# MB_RELAY.net
KiCad netlist of a schematic drawn in Altium Designer
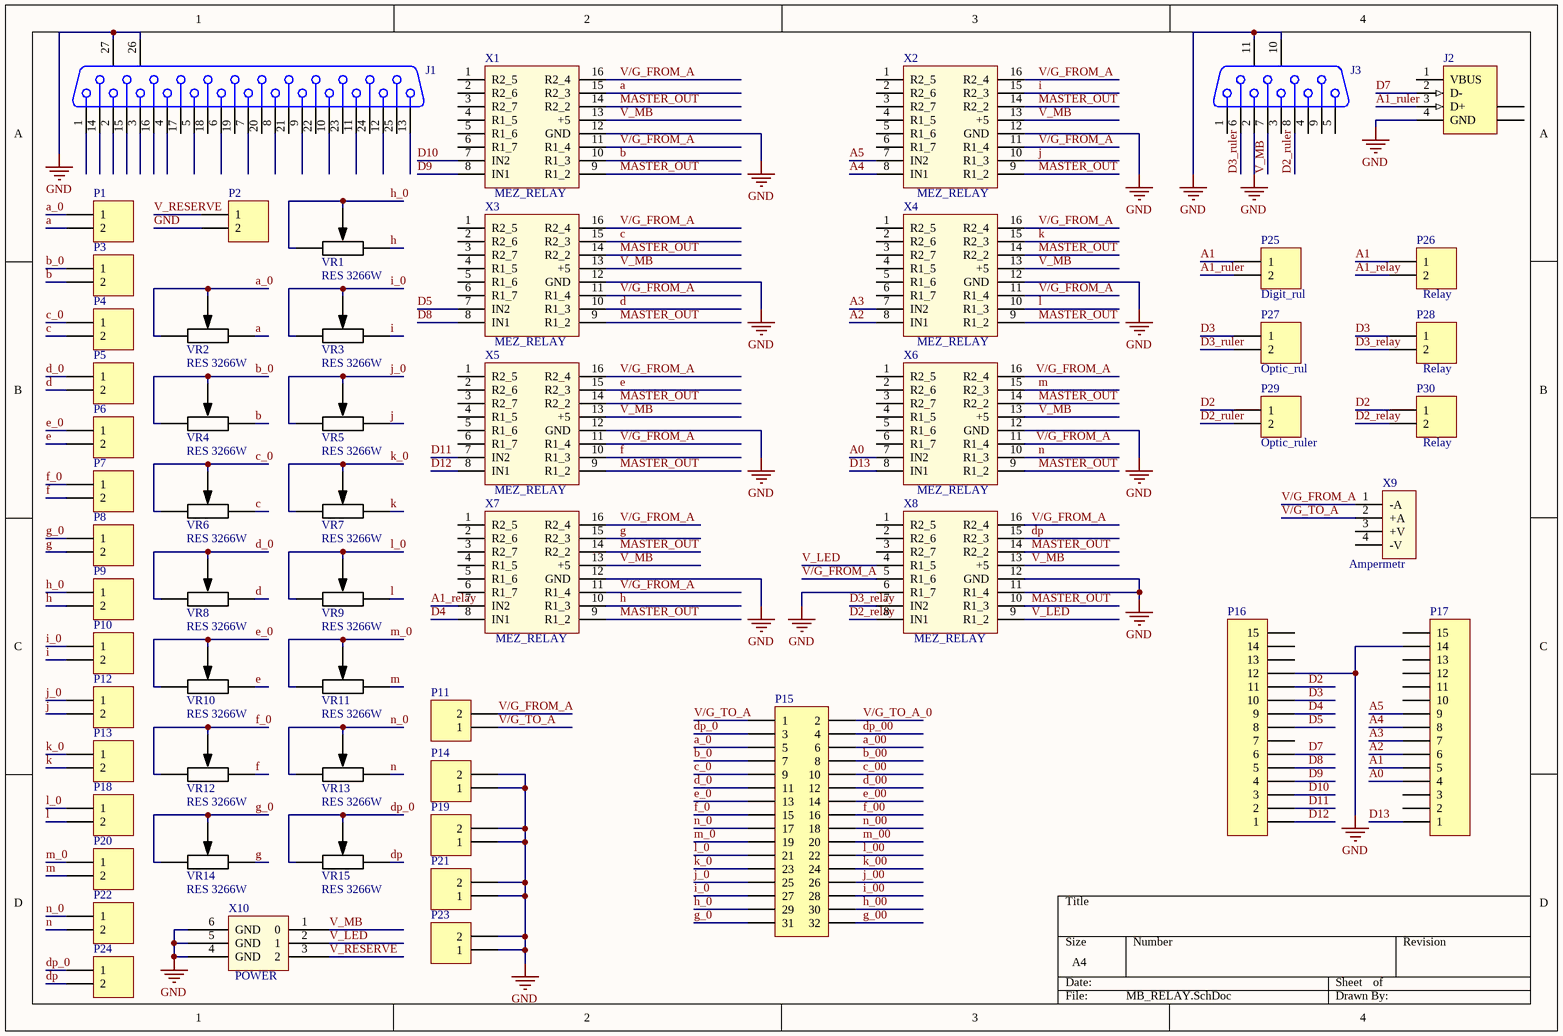
[diagram p0: MB_RELAY.SchDoc]

(export (version "E")
  (design (tool "Eeschema 10.0.6"))
  (components
    (comp (ref "J1")
      (value "D Connector 25")
      (footprint "DSUB1.385-2H25A")
      (description "Receptacle Assembly, 25 Position, Right Angle")
      (fields (field (name "PUBLISHER") "Altium Limited"))
      (libsource (lib "Miscellaneous Connectors") (part "D Connector 25"))
    )
    (comp (ref "J2")
      (value "1-353576-1")
      (footprint "353576")
      (description "USB 1.1, Right Angle, SMT, A Type, Receptacle, 4 Position, White")
      (fields (field (name "PUBLISHER") "Altium Limited"))
      (libsource (lib "AMP Serial Bus USB") (part "1-353576-1"))
    )
    (comp (ref "J3")
      (value "D Connector 9")
      (footprint "DSUB1.385-2H9")
      (description "Receptacle Assembly, 9 Position, Right Angle")
      (fields (field (name "PUBLISHER") "Altium Limited"))
      (libsource (lib "Miscellaneous Connectors") (part "D Connector 9"))
    )
    (comp (ref "P1")
      (value "Header 2")
      (footprint "HDR1X2")
      (description "Header, 2-Pin")
      (fields (field (name "PUBLISHER") "Altium Limited"))
      (libsource (lib "Miscellaneous Connectors") (part "Header 2"))
    )
    (comp (ref "P2")
      (value "Header 2")
      (footprint "HDR1X2")
      (description "Header, 2-Pin")
      (fields (field (name "PUBLISHER") "Altium Limited"))
      (libsource (lib "Miscellaneous Connectors") (part "Header 2"))
    )
    (comp (ref "P3")
      (value "Header 2")
      (footprint "HDR1X2")
      (description "Header, 2-Pin")
      (fields (field (name "PUBLISHER") "Altium Limited"))
      (libsource (lib "Miscellaneous Connectors") (part "Header 2"))
    )
    (comp (ref "P4")
      (value "Header 2")
      (footprint "HDR1X2")
      (description "Header, 2-Pin")
      (fields (field (name "PUBLISHER") "Altium Limited"))
      (libsource (lib "Miscellaneous Connectors") (part "Header 2"))
    )
    (comp (ref "P5")
      (value "Header 2")
      (footprint "HDR1X2")
      (description "Header, 2-Pin")
      (fields (field (name "PUBLISHER") "Altium Limited"))
      (libsource (lib "Miscellaneous Connectors") (part "Header 2"))
    )
    (comp (ref "P6")
      (value "GND")
      (footprint "HDR1X2")
      (description "Header, 2-Pin")
      (fields (field (name "PUBLISHER") "Altium Limited"))
      (libsource (lib "Miscellaneous Connectors") (part "Header 2"))
    )
    (comp (ref "P7")
      (value "GND")
      (footprint "HDR1X2")
      (description "Header, 2-Pin")
      (fields (field (name "PUBLISHER") "Altium Limited"))
      (libsource (lib "Miscellaneous Connectors") (part "Header 2"))
    )
    (comp (ref "P8")
      (value "GND")
      (footprint "HDR1X2")
      (description "Header, 2-Pin")
      (fields (field (name "PUBLISHER") "Altium Limited"))
      (libsource (lib "Miscellaneous Connectors") (part "Header 2"))
    )
    (comp (ref "P9")
      (value "GND")
      (footprint "HDR1X2")
      (description "Header, 2-Pin")
      (fields (field (name "PUBLISHER") "Altium Limited"))
      (libsource (lib "Miscellaneous Connectors") (part "Header 2"))
    )
    (comp (ref "P10")
      (value "Header 2")
      (footprint "HDR1X2")
      (description "Header, 2-Pin")
      (fields (field (name "PUBLISHER") "Altium Limited"))
      (libsource (lib "Miscellaneous Connectors") (part "Header 2"))
    )
    (comp (ref "P11")
      (value "Header 2")
      (footprint "HDR1X2")
      (description "Header, 2-Pin")
      (fields (field (name "PUBLISHER") "Altium Limited"))
      (libsource (lib "") (part "Header 2_1"))
    )
    (comp (ref "P12")
      (value "Header 2")
      (footprint "HDR1X2")
      (description "Header, 2-Pin")
      (fields (field (name "PUBLISHER") "Altium Limited"))
      (libsource (lib "Miscellaneous Connectors") (part "Header 2"))
    )
    (comp (ref "P13")
      (value "GND")
      (footprint "HDR1X2")
      (description "Header, 2-Pin")
      (fields (field (name "PUBLISHER") "Altium Limited"))
      (libsource (lib "Miscellaneous Connectors") (part "Header 2"))
    )
    (comp (ref "P14")
      (value "GND")
      (footprint "HDR1X2")
      (description "Header, 2-Pin")
      (fields (field (name "PUBLISHER") "Altium Limited"))
      (libsource (lib "") (part "Header 2_1"))
    )
    (comp (ref "P15")
      (value "Header 16X2")
      (footprint "HDR2X16")
      (description "Header, 16-Pin, Dual row")
      (fields (field (name "PUBLISHER") "Altium Limited"))
      (libsource (lib "Miscellaneous Connectors") (part "Header 16X2"))
    )
    (comp (ref "P16")
      (value "Header 15")
      (footprint "HDR1X15")
      (description "Header, 15-Pin")
      (fields (field (name "PUBLISHER") "Altium Limited"))
      (libsource (lib "") (part "Header 15_1"))
    )
    (comp (ref "P17")
      (value "Header 15")
      (footprint "HDR1X15")
      (description "Header, 15-Pin")
      (fields (field (name "PUBLISHER") "Altium Limited"))
      (libsource (lib "Miscellaneous Connectors") (part "Header 15"))
    )
    (comp (ref "P18")
      (value "GND")
      (footprint "HDR1X2")
      (description "Header, 2-Pin")
      (fields (field (name "PUBLISHER") "Altium Limited"))
      (libsource (lib "Miscellaneous Connectors") (part "Header 2"))
    )
    (comp (ref "P19")
      (value "GND")
      (footprint "HDR1X2")
      (description "Header, 2-Pin")
      (fields (field (name "PUBLISHER") "Altium Limited"))
      (libsource (lib "") (part "Header 2_1"))
    )
    (comp (ref "P20")
      (value "GND")
      (footprint "HDR1X2")
      (description "Header, 2-Pin")
      (fields (field (name "PUBLISHER") "Altium Limited"))
      (libsource (lib "Miscellaneous Connectors") (part "Header 2"))
    )
    (comp (ref "P21")
      (value "GND")
      (footprint "HDR1X2")
      (description "Header, 2-Pin")
      (fields (field (name "PUBLISHER") "Altium Limited"))
      (libsource (lib "") (part "Header 2_1"))
    )
    (comp (ref "P22")
      (value "GND")
      (footprint "HDR1X2")
      (description "Header, 2-Pin")
      (fields (field (name "PUBLISHER") "Altium Limited"))
      (libsource (lib "Miscellaneous Connectors") (part "Header 2"))
    )
    (comp (ref "P23")
      (value "GND")
      (footprint "HDR1X2")
      (description "Header, 2-Pin")
      (fields (field (name "PUBLISHER") "Altium Limited"))
      (libsource (lib "") (part "Header 2_1"))
    )
    (comp (ref "P24")
      (value "GND")
      (footprint "HDR1X2")
      (description "Header, 2-Pin")
      (fields (field (name "PUBLISHER") "Altium Limited"))
      (libsource (lib "Miscellaneous Connectors") (part "Header 2"))
    )
    (comp (ref "P25")
      (value "Digit_rul")
      (footprint "HDR1X2")
      (description "Header, 2-Pin")
      (fields (field (name "PUBLISHER") "Altium Limited"))
      (libsource (lib "Miscellaneous Connectors") (part "Header 2"))
    )
    (comp (ref "P26")
      (value "Relay")
      (footprint "HDR1X2")
      (description "Header, 2-Pin")
      (fields (field (name "PUBLISHER") "Altium Limited"))
      (libsource (lib "Miscellaneous Connectors") (part "Header 2"))
    )
    (comp (ref "P27")
      (value "Optic_rul")
      (footprint "HDR1X2")
      (description "Header, 2-Pin")
      (fields (field (name "PUBLISHER") "Altium Limited"))
      (libsource (lib "Miscellaneous Connectors") (part "Header 2"))
    )
    (comp (ref "P28")
      (value "Relay")
      (footprint "HDR1X2")
      (description "Header, 2-Pin")
      (fields (field (name "PUBLISHER") "Altium Limited"))
      (libsource (lib "Miscellaneous Connectors") (part "Header 2"))
    )
    (comp (ref "P29")
      (value "Optic_ruler")
      (footprint "HDR1X2")
      (description "Header, 2-Pin")
      (fields (field (name "PUBLISHER") "Altium Limited"))
      (libsource (lib "Miscellaneous Connectors") (part "Header 2"))
    )
    (comp (ref "P30")
      (value "Relay")
      (footprint "HDR1X2")
      (description "Header, 2-Pin")
      (fields (field (name "PUBLISHER") "Altium Limited"))
      (libsource (lib "Miscellaneous Connectors") (part "Header 2"))
    )
    (comp (ref "VR1")
      (value "RES 3266W")
      (footprint "aab_Passive:RES 3266W")
      (libsource (lib "aab_Schlib") (part "RES 3266W"))
    )
    (comp (ref "VR2")
      (value "RES 3266W")
      (footprint "aab_Passive:RES 3266W")
      (libsource (lib "aab_Schlib") (part "RES 3266W"))
    )
    (comp (ref "VR3")
      (value "RES 3266W")
      (footprint "aab_Passive:RES 3266W")
      (libsource (lib "aab_Schlib") (part "RES 3266W"))
    )
    (comp (ref "VR4")
      (value "RES 3266W")
      (footprint "aab_Passive:RES 3266W")
      (libsource (lib "aab_Schlib") (part "RES 3266W"))
    )
    (comp (ref "VR5")
      (value "RES 3266W")
      (footprint "aab_Passive:RES 3266W")
      (libsource (lib "aab_Schlib") (part "RES 3266W"))
    )
    (comp (ref "VR6")
      (value "RES 3266W")
      (footprint "aab_Passive:RES 3266W")
      (libsource (lib "aab_Schlib") (part "RES 3266W"))
    )
    (comp (ref "VR7")
      (value "RES 3266W")
      (footprint "aab_Passive:RES 3266W")
      (libsource (lib "aab_Schlib") (part "RES 3266W"))
    )
    (comp (ref "VR8")
      (value "RES 3266W")
      (footprint "aab_Passive:RES 3266W")
      (libsource (lib "aab_Schlib") (part "RES 3266W"))
    )
    (comp (ref "VR9")
      (value "RES 3266W")
      (footprint "aab_Passive:RES 3266W")
      (libsource (lib "aab_Schlib") (part "RES 3266W"))
    )
    (comp (ref "VR10")
      (value "RES 3266W")
      (footprint "aab_Passive:RES 3266W")
      (libsource (lib "aab_Schlib") (part "RES 3266W"))
    )
    (comp (ref "VR11")
      (value "RES 3266W")
      (footprint "aab_Passive:RES 3266W")
      (libsource (lib "aab_Schlib") (part "RES 3266W"))
    )
    (comp (ref "VR12")
      (value "RES 3266W")
      (footprint "aab_Passive:RES 3266W")
      (libsource (lib "aab_Schlib") (part "RES 3266W"))
    )
    (comp (ref "VR13")
      (value "RES 3266W")
      (footprint "aab_Passive:RES 3266W")
      (libsource (lib "aab_Schlib") (part "RES 3266W"))
    )
    (comp (ref "VR14")
      (value "RES 3266W")
      (footprint "aab_Passive:RES 3266W")
      (libsource (lib "aab_Schlib") (part "RES 3266W"))
    )
    (comp (ref "VR15")
      (value "RES 3266W")
      (footprint "aab_Passive:RES 3266W")
      (libsource (lib "aab_Schlib") (part "RES 3266W"))
    )
    (comp (ref "X1")
      (value "MEZ_RELAY")
      (footprint "MEZ_RELAY")
      (libsource (lib "msp_SchLib") (part "MEZ_RELAY"))
    )
    (comp (ref "X2")
      (value "MEZ_RELAY")
      (footprint "MEZ_RELAY")
      (libsource (lib "msp_SchLib") (part "MEZ_RELAY"))
    )
    (comp (ref "X3")
      (value "MEZ_RELAY")
      (footprint "MEZ_RELAY")
      (libsource (lib "msp_SchLib") (part "MEZ_RELAY"))
    )
    (comp (ref "X4")
      (value "MEZ_RELAY")
      (footprint "MEZ_RELAY")
      (libsource (lib "msp_SchLib") (part "MEZ_RELAY"))
    )
    (comp (ref "X5")
      (value "MEZ_RELAY")
      (footprint "MEZ_RELAY")
      (libsource (lib "msp_SchLib") (part "MEZ_RELAY"))
    )
    (comp (ref "X6")
      (value "MEZ_RELAY")
      (footprint "MEZ_RELAY")
      (libsource (lib "msp_SchLib") (part "MEZ_RELAY"))
    )
    (comp (ref "X7")
      (value "MEZ_RELAY")
      (footprint "MEZ_RELAY")
      (libsource (lib "msp_SchLib") (part "MEZ_RELAY"))
    )
    (comp (ref "X8")
      (value "MEZ_RELAY")
      (footprint "MEZ_RELAY")
      (libsource (lib "msp_SchLib") (part "MEZ_RELAY"))
    )
    (comp (ref "X9")
      (value "Ampermetr")
      (footprint "vpl_Passive:AMP_VOLTMETER")
      (libsource (lib "msp_SchLib") (part "AMP_VOLTMETR"))
    )
    (comp (ref "X10")
      (value "POWER")
      (footprint "vpl_Passive:POWER")
      (libsource (lib "msp_SchLib") (part "POWER"))
    )
  )
  (nets
    (net (code "1") (name "/A0") (class "Default")
      (node (ref "P17") (pin "4") (pinfunction "4_4") (pintype "passive"))
      (node (ref "X6") (pin "7") (pinfunction "IN2_7") (pintype "passive"))
    )
    (net (code "2") (name "/A1") (class "Default")
      (node (ref "P17") (pin "5") (pinfunction "5_5") (pintype "passive"))
      (node (ref "P25") (pin "1") (pinfunction "1_1") (pintype "passive"))
      (node (ref "P26") (pin "1") (pinfunction "1_1") (pintype "passive"))
    )
    (net (code "3") (name "/A1_relay") (class "Default")
      (node (ref "P26") (pin "2") (pinfunction "2_2") (pintype "passive"))
      (node (ref "X7") (pin "7") (pinfunction "IN2_7") (pintype "passive"))
    )
    (net (code "4") (name "/A1_ruler") (class "Default")
      (node (ref "J2") (pin "3") (pinfunction "D+_3") (pintype "input"))
      (node (ref "P25") (pin "2") (pinfunction "2_2") (pintype "passive"))
    )
    (net (code "5") (name "/A2") (class "Default")
      (node (ref "P17") (pin "6") (pinfunction "6_6") (pintype "passive"))
      (node (ref "X4") (pin "8") (pinfunction "IN1_8") (pintype "passive"))
    )
    (net (code "6") (name "/A3") (class "Default")
      (node (ref "P17") (pin "7") (pinfunction "7_7") (pintype "passive"))
      (node (ref "X4") (pin "7") (pinfunction "IN2_7") (pintype "passive"))
    )
    (net (code "7") (name "/A4") (class "Default")
      (node (ref "P17") (pin "8") (pinfunction "8_8") (pintype "passive"))
      (node (ref "X2") (pin "8") (pinfunction "IN1_8") (pintype "passive"))
    )
    (net (code "8") (name "/A5") (class "Default")
      (node (ref "P17") (pin "9") (pinfunction "9_9") (pintype "passive"))
      (node (ref "X2") (pin "7") (pinfunction "IN2_7") (pintype "passive"))
    )
    (net (code "9") (name "/D2") (class "Default")
      (node (ref "P16") (pin "11") (pinfunction "11_11") (pintype "passive"))
      (node (ref "P29") (pin "1") (pinfunction "1_1") (pintype "passive"))
      (node (ref "P30") (pin "1") (pinfunction "1_1") (pintype "passive"))
    )
    (net (code "10") (name "/D2_relay") (class "Default")
      (node (ref "P30") (pin "2") (pinfunction "2_2") (pintype "passive"))
      (node (ref "X8") (pin "8") (pinfunction "IN1_8") (pintype "passive"))
    )
    (net (code "11") (name "/D2_ruler") (class "Default")
      (node (ref "J3") (pin "8") (pinfunction "8_8") (pintype "passive"))
      (node (ref "P29") (pin "2") (pinfunction "2_2") (pintype "passive"))
    )
    (net (code "12") (name "/D3") (class "Default")
      (node (ref "P16") (pin "10") (pinfunction "10_10") (pintype "passive"))
      (node (ref "P27") (pin "1") (pinfunction "1_1") (pintype "passive"))
      (node (ref "P28") (pin "1") (pinfunction "1_1") (pintype "passive"))
    )
    (net (code "13") (name "/D3_relay") (class "Default")
      (node (ref "P28") (pin "2") (pinfunction "2_2") (pintype "passive"))
      (node (ref "X8") (pin "7") (pinfunction "IN2_7") (pintype "passive"))
    )
    (net (code "14") (name "/D3_ruler") (class "Default")
      (node (ref "J3") (pin "6") (pinfunction "6_6") (pintype "passive"))
      (node (ref "P27") (pin "2") (pinfunction "2_2") (pintype "passive"))
    )
    (net (code "15") (name "/D4") (class "Default")
      (node (ref "P16") (pin "9") (pinfunction "9_9") (pintype "passive"))
      (node (ref "X7") (pin "8") (pinfunction "IN1_8") (pintype "passive"))
    )
    (net (code "16") (name "/D5") (class "Default")
      (node (ref "P16") (pin "8") (pinfunction "8_8") (pintype "passive"))
      (node (ref "X3") (pin "7") (pinfunction "IN2_7") (pintype "passive"))
    )
    (net (code "17") (name "/D7") (class "Default")
      (node (ref "J2") (pin "2") (pinfunction "D-_2") (pintype "input"))
      (node (ref "P16") (pin "6") (pinfunction "6_6") (pintype "passive"))
    )
    (net (code "18") (name "/D8") (class "Default")
      (node (ref "P16") (pin "5") (pinfunction "5_5") (pintype "passive"))
      (node (ref "X3") (pin "8") (pinfunction "IN1_8") (pintype "passive"))
    )
    (net (code "19") (name "/D9") (class "Default")
      (node (ref "P16") (pin "4") (pinfunction "4_4") (pintype "passive"))
      (node (ref "X1") (pin "8") (pinfunction "IN1_8") (pintype "passive"))
    )
    (net (code "20") (name "/D10") (class "Default")
      (node (ref "P16") (pin "3") (pinfunction "3_3") (pintype "passive"))
      (node (ref "X1") (pin "7") (pinfunction "IN2_7") (pintype "passive"))
    )
    (net (code "21") (name "/D11") (class "Default")
      (node (ref "P16") (pin "2") (pinfunction "2_2") (pintype "passive"))
      (node (ref "X5") (pin "7") (pinfunction "IN2_7") (pintype "passive"))
    )
    (net (code "22") (name "/D12") (class "Default")
      (node (ref "P16") (pin "1") (pinfunction "1_1") (pintype "passive"))
      (node (ref "X5") (pin "8") (pinfunction "IN1_8") (pintype "passive"))
    )
    (net (code "23") (name "/D13") (class "Default")
      (node (ref "P17") (pin "1") (pinfunction "1_1") (pintype "passive"))
      (node (ref "X6") (pin "8") (pinfunction "IN1_8") (pintype "passive"))
    )
    (net (code "24") (name "/MASTER_OUT") (class "Default")
      (node (ref "X1") (pin "14") (pinfunction "R2_2_14") (pintype "passive"))
      (node (ref "X1") (pin "9") (pinfunction "R1_2_9") (pintype "passive"))
      (node (ref "X2") (pin "14") (pinfunction "R2_2_14") (pintype "passive"))
      (node (ref "X2") (pin "9") (pinfunction "R1_2_9") (pintype "passive"))
      (node (ref "X3") (pin "14") (pinfunction "R2_2_14") (pintype "passive"))
      (node (ref "X3") (pin "9") (pinfunction "R1_2_9") (pintype "passive"))
      (node (ref "X4") (pin "14") (pinfunction "R2_2_14") (pintype "passive"))
      (node (ref "X4") (pin "9") (pinfunction "R1_2_9") (pintype "passive"))
      (node (ref "X5") (pin "14") (pinfunction "R2_2_14") (pintype "passive"))
      (node (ref "X5") (pin "9") (pinfunction "R1_2_9") (pintype "passive"))
      (node (ref "X6") (pin "14") (pinfunction "R2_2_14") (pintype "passive"))
      (node (ref "X6") (pin "9") (pinfunction "R1_2_9") (pintype "passive"))
      (node (ref "X7") (pin "14") (pinfunction "R2_2_14") (pintype "passive"))
      (node (ref "X7") (pin "9") (pinfunction "R1_2_9") (pintype "passive"))
      (node (ref "X8") (pin "10") (pinfunction "R1_3_10") (pintype "passive"))
      (node (ref "X8") (pin "14") (pinfunction "R2_2_14") (pintype "passive"))
    )
    (net (code "25") (name "/V_LED") (class "Default")
      (node (ref "X10") (pin "2") (pinfunction "1_2") (pintype "passive"))
      (node (ref "X8") (pin "4") (pinfunction "R1_5_4") (pintype "passive"))
      (node (ref "X8") (pin "9") (pinfunction "R1_2_9") (pintype "passive"))
    )
    (net (code "26") (name "/V_MB") (class "Default")
      (node (ref "J3") (pin "7") (pinfunction "7_7") (pintype "passive"))
      (node (ref "X1") (pin "13") (pinfunction "+5_13") (pintype "passive"))
      (node (ref "X10") (pin "1") (pinfunction "0_1") (pintype "passive"))
      (node (ref "X2") (pin "13") (pinfunction "+5_13") (pintype "passive"))
      (node (ref "X3") (pin "13") (pinfunction "+5_13") (pintype "passive"))
      (node (ref "X4") (pin "13") (pinfunction "+5_13") (pintype "passive"))
      (node (ref "X5") (pin "13") (pinfunction "+5_13") (pintype "passive"))
      (node (ref "X6") (pin "13") (pinfunction "+5_13") (pintype "passive"))
      (node (ref "X7") (pin "13") (pinfunction "+5_13") (pintype "passive"))
      (node (ref "X8") (pin "13") (pinfunction "+5_13") (pintype "passive"))
    )
    (net (code "27") (name "/V_RESERVE") (class "Default")
      (node (ref "P2") (pin "1") (pinfunction "1_1") (pintype "passive"))
      (node (ref "X10") (pin "3") (pinfunction "2_3") (pintype "passive"))
    )
    (net (code "28") (name "/V{slash}G_FROM_A") (class "Default")
      (node (ref "P11") (pin "2") (pinfunction "2_2") (pintype "passive"))
      (node (ref "X1") (pin "11") (pinfunction "R1_4_11") (pintype "passive"))
      (node (ref "X1") (pin "16") (pinfunction "R2_4_16") (pintype "passive"))
      (node (ref "X2") (pin "11") (pinfunction "R1_4_11") (pintype "passive"))
      (node (ref "X2") (pin "16") (pinfunction "R2_4_16") (pintype "passive"))
      (node (ref "X3") (pin "11") (pinfunction "R1_4_11") (pintype "passive"))
      (node (ref "X3") (pin "16") (pinfunction "R2_4_16") (pintype "passive"))
      (node (ref "X4") (pin "11") (pinfunction "R1_4_11") (pintype "passive"))
      (node (ref "X4") (pin "16") (pinfunction "R2_4_16") (pintype "passive"))
      (node (ref "X5") (pin "11") (pinfunction "R1_4_11") (pintype "passive"))
      (node (ref "X5") (pin "16") (pinfunction "R2_4_16") (pintype "passive"))
      (node (ref "X6") (pin "11") (pinfunction "R1_4_11") (pintype "passive"))
      (node (ref "X6") (pin "16") (pinfunction "R2_4_16") (pintype "passive"))
      (node (ref "X7") (pin "11") (pinfunction "R1_4_11") (pintype "passive"))
      (node (ref "X7") (pin "16") (pinfunction "R2_4_16") (pintype "passive"))
      (node (ref "X8") (pin "16") (pinfunction "R2_4_16") (pintype "passive"))
      (node (ref "X8") (pin "5") (pinfunction "R1_6_5") (pintype "passive"))
      (node (ref "X9") (pin "1") (pinfunction "-A_1") (pintype "passive"))
    )
    (net (code "29") (name "/V{slash}G_TO_A") (class "Default")
      (node (ref "P11") (pin "1") (pinfunction "1_1") (pintype "passive"))
      (node (ref "P15") (pin "1") (pinfunction "1_1") (pintype "passive"))
      (node (ref "X9") (pin "2") (pinfunction "+A_2") (pintype "passive"))
    )
    (net (code "30") (name "/V{slash}G_TO_A_0") (class "Default")
      (node (ref "P15") (pin "2") (pinfunction "2_2") (pintype "passive"))
    )
    (net (code "31") (name "/a") (class "Default")
      (node (ref "P1") (pin "2") (pinfunction "2_2") (pintype "passive"))
      (node (ref "VR2") (pin "3") (pinfunction "3_3") (pintype "passive"))
      (node (ref "X1") (pin "15") (pinfunction "R2_3_15") (pintype "passive"))
    )
    (net (code "32") (name "/a_0") (class "Default")
      (node (ref "P1") (pin "1") (pinfunction "1_1") (pintype "passive"))
      (node (ref "P15") (pin "5") (pinfunction "5_5") (pintype "passive"))
      (node (ref "VR2") (pin "1") (pinfunction "1_1") (pintype "passive"))
      (node (ref "VR2") (pin "2") (pinfunction "2_2") (pintype "passive"))
    )
    (net (code "33") (name "/a_00") (class "Default")
      (node (ref "P15") (pin "6") (pinfunction "6_6") (pintype "passive"))
    )
    (net (code "34") (name "/b") (class "Default")
      (node (ref "P3") (pin "2") (pinfunction "2_2") (pintype "passive"))
      (node (ref "VR4") (pin "3") (pinfunction "3_3") (pintype "passive"))
      (node (ref "X1") (pin "10") (pinfunction "R1_3_10") (pintype "passive"))
    )
    (net (code "35") (name "/b_00") (class "Default")
      (node (ref "P15") (pin "8") (pinfunction "8_8") (pintype "passive"))
    )
    (net (code "36") (name "/b_0") (class "Default")
      (node (ref "P15") (pin "7") (pinfunction "7_7") (pintype "passive"))
      (node (ref "P3") (pin "1") (pinfunction "1_1") (pintype "passive"))
      (node (ref "VR4") (pin "1") (pinfunction "1_1") (pintype "passive"))
      (node (ref "VR4") (pin "2") (pinfunction "2_2") (pintype "passive"))
    )
    (net (code "37") (name "/c") (class "Default")
      (node (ref "P4") (pin "2") (pinfunction "2_2") (pintype "passive"))
      (node (ref "VR6") (pin "3") (pinfunction "3_3") (pintype "passive"))
      (node (ref "X3") (pin "15") (pinfunction "R2_3_15") (pintype "passive"))
    )
    (net (code "38") (name "/c_0") (class "Default")
      (node (ref "P15") (pin "9") (pinfunction "9_9") (pintype "passive"))
      (node (ref "P4") (pin "1") (pinfunction "1_1") (pintype "passive"))
      (node (ref "VR6") (pin "1") (pinfunction "1_1") (pintype "passive"))
      (node (ref "VR6") (pin "2") (pinfunction "2_2") (pintype "passive"))
    )
    (net (code "39") (name "/c_00") (class "Default")
      (node (ref "P15") (pin "10") (pinfunction "10_10") (pintype "passive"))
    )
    (net (code "40") (name "/d") (class "Default")
      (node (ref "P5") (pin "2") (pinfunction "2_2") (pintype "passive"))
      (node (ref "VR8") (pin "3") (pinfunction "3_3") (pintype "passive"))
      (node (ref "X3") (pin "10") (pinfunction "R1_3_10") (pintype "passive"))
    )
    (net (code "41") (name "/d_00") (class "Default")
      (node (ref "P15") (pin "12") (pinfunction "12_12") (pintype "passive"))
    )
    (net (code "42") (name "/d_0") (class "Default")
      (node (ref "P15") (pin "11") (pinfunction "11_11") (pintype "passive"))
      (node (ref "P5") (pin "1") (pinfunction "1_1") (pintype "passive"))
      (node (ref "VR8") (pin "1") (pinfunction "1_1") (pintype "passive"))
      (node (ref "VR8") (pin "2") (pinfunction "2_2") (pintype "passive"))
    )
    (net (code "43") (name "/dp") (class "Default")
      (node (ref "P24") (pin "2") (pinfunction "2_2") (pintype "passive"))
      (node (ref "VR15") (pin "3") (pinfunction "3_3") (pintype "passive"))
      (node (ref "X8") (pin "15") (pinfunction "R2_3_15") (pintype "passive"))
    )
    (net (code "44") (name "/dp_00") (class "Default")
      (node (ref "P15") (pin "4") (pinfunction "4_4") (pintype "passive"))
    )
    (net (code "45") (name "/dp_0") (class "Default")
      (node (ref "P15") (pin "3") (pinfunction "3_3") (pintype "passive"))
      (node (ref "P24") (pin "1") (pinfunction "1_1") (pintype "passive"))
      (node (ref "VR15") (pin "1") (pinfunction "1_1") (pintype "passive"))
      (node (ref "VR15") (pin "2") (pinfunction "2_2") (pintype "passive"))
    )
    (net (code "46") (name "/e") (class "Default")
      (node (ref "P6") (pin "2") (pinfunction "2_2") (pintype "passive"))
      (node (ref "VR10") (pin "3") (pinfunction "3_3") (pintype "passive"))
      (node (ref "X5") (pin "15") (pinfunction "R2_3_15") (pintype "passive"))
    )
    (net (code "47") (name "/e_0") (class "Default")
      (node (ref "P15") (pin "13") (pinfunction "13_13") (pintype "passive"))
      (node (ref "P6") (pin "1") (pinfunction "1_1") (pintype "passive"))
      (node (ref "VR10") (pin "1") (pinfunction "1_1") (pintype "passive"))
      (node (ref "VR10") (pin "2") (pinfunction "2_2") (pintype "passive"))
    )
    (net (code "48") (name "/e_00") (class "Default")
      (node (ref "P15") (pin "14") (pinfunction "14_14") (pintype "passive"))
    )
    (net (code "49") (name "/f") (class "Default")
      (node (ref "P7") (pin "2") (pinfunction "2_2") (pintype "passive"))
      (node (ref "VR12") (pin "3") (pinfunction "3_3") (pintype "passive"))
      (node (ref "X5") (pin "10") (pinfunction "R1_3_10") (pintype "passive"))
    )
    (net (code "50") (name "/f_00") (class "Default")
      (node (ref "P15") (pin "16") (pinfunction "16_16") (pintype "passive"))
    )
    (net (code "51") (name "/f_0") (class "Default")
      (node (ref "P15") (pin "15") (pinfunction "15_15") (pintype "passive"))
      (node (ref "P7") (pin "1") (pinfunction "1_1") (pintype "passive"))
      (node (ref "VR12") (pin "1") (pinfunction "1_1") (pintype "passive"))
      (node (ref "VR12") (pin "2") (pinfunction "2_2") (pintype "passive"))
    )
    (net (code "52") (name "/g") (class "Default")
      (node (ref "P8") (pin "2") (pinfunction "2_2") (pintype "passive"))
      (node (ref "VR14") (pin "3") (pinfunction "3_3") (pintype "passive"))
      (node (ref "X7") (pin "15") (pinfunction "R2_3_15") (pintype "passive"))
    )
    (net (code "53") (name "/g_0") (class "Default")
      (node (ref "P15") (pin "31") (pinfunction "31_31") (pintype "passive"))
      (node (ref "P8") (pin "1") (pinfunction "1_1") (pintype "passive"))
      (node (ref "VR14") (pin "1") (pinfunction "1_1") (pintype "passive"))
      (node (ref "VR14") (pin "2") (pinfunction "2_2") (pintype "passive"))
    )
    (net (code "54") (name "/g_00") (class "Default")
      (node (ref "P15") (pin "32") (pinfunction "32_32") (pintype "passive"))
    )
    (net (code "55") (name "/h") (class "Default")
      (node (ref "P9") (pin "2") (pinfunction "2_2") (pintype "passive"))
      (node (ref "VR1") (pin "3") (pinfunction "3_3") (pintype "passive"))
      (node (ref "X7") (pin "10") (pinfunction "R1_3_10") (pintype "passive"))
    )
    (net (code "56") (name "/h_0") (class "Default")
      (node (ref "P15") (pin "29") (pinfunction "29_29") (pintype "passive"))
      (node (ref "P9") (pin "1") (pinfunction "1_1") (pintype "passive"))
      (node (ref "VR1") (pin "1") (pinfunction "1_1") (pintype "passive"))
      (node (ref "VR1") (pin "2") (pinfunction "2_2") (pintype "passive"))
    )
    (net (code "57") (name "/h_00") (class "Default")
      (node (ref "P15") (pin "30") (pinfunction "30_30") (pintype "passive"))
    )
    (net (code "58") (name "/i") (class "Default")
      (node (ref "P10") (pin "2") (pinfunction "2_2") (pintype "passive"))
      (node (ref "VR3") (pin "3") (pinfunction "3_3") (pintype "passive"))
      (node (ref "X2") (pin "15") (pinfunction "R2_3_15") (pintype "passive"))
    )
    (net (code "59") (name "/i_00") (class "Default")
      (node (ref "P15") (pin "28") (pinfunction "28_28") (pintype "passive"))
    )
    (net (code "60") (name "/i_0") (class "Default")
      (node (ref "P10") (pin "1") (pinfunction "1_1") (pintype "passive"))
      (node (ref "P15") (pin "27") (pinfunction "27_27") (pintype "passive"))
      (node (ref "VR3") (pin "1") (pinfunction "1_1") (pintype "passive"))
      (node (ref "VR3") (pin "2") (pinfunction "2_2") (pintype "passive"))
    )
    (net (code "61") (name "/j") (class "Default")
      (node (ref "P12") (pin "2") (pinfunction "2_2") (pintype "passive"))
      (node (ref "VR5") (pin "3") (pinfunction "3_3") (pintype "passive"))
      (node (ref "X2") (pin "10") (pinfunction "R1_3_10") (pintype "passive"))
    )
    (net (code "62") (name "/j_0") (class "Default")
      (node (ref "P12") (pin "1") (pinfunction "1_1") (pintype "passive"))
      (node (ref "P15") (pin "25") (pinfunction "25_25") (pintype "passive"))
      (node (ref "VR5") (pin "1") (pinfunction "1_1") (pintype "passive"))
      (node (ref "VR5") (pin "2") (pinfunction "2_2") (pintype "passive"))
    )
    (net (code "63") (name "/j_00") (class "Default")
      (node (ref "P15") (pin "26") (pinfunction "26_26") (pintype "passive"))
    )
    (net (code "64") (name "/k") (class "Default")
      (node (ref "P13") (pin "2") (pinfunction "2_2") (pintype "passive"))
      (node (ref "VR7") (pin "3") (pinfunction "3_3") (pintype "passive"))
      (node (ref "X4") (pin "15") (pinfunction "R2_3_15") (pintype "passive"))
    )
    (net (code "65") (name "/k_0") (class "Default")
      (node (ref "P13") (pin "1") (pinfunction "1_1") (pintype "passive"))
      (node (ref "P15") (pin "23") (pinfunction "23_23") (pintype "passive"))
      (node (ref "VR7") (pin "1") (pinfunction "1_1") (pintype "passive"))
      (node (ref "VR7") (pin "2") (pinfunction "2_2") (pintype "passive"))
    )
    (net (code "66") (name "/k_00") (class "Default")
      (node (ref "P15") (pin "24") (pinfunction "24_24") (pintype "passive"))
    )
    (net (code "67") (name "/l") (class "Default")
      (node (ref "P18") (pin "2") (pinfunction "2_2") (pintype "passive"))
      (node (ref "VR9") (pin "3") (pinfunction "3_3") (pintype "passive"))
      (node (ref "X4") (pin "10") (pinfunction "R1_3_10") (pintype "passive"))
    )
    (net (code "68") (name "/l_0") (class "Default")
      (node (ref "P15") (pin "21") (pinfunction "21_21") (pintype "passive"))
      (node (ref "P18") (pin "1") (pinfunction "1_1") (pintype "passive"))
      (node (ref "VR9") (pin "1") (pinfunction "1_1") (pintype "passive"))
      (node (ref "VR9") (pin "2") (pinfunction "2_2") (pintype "passive"))
    )
    (net (code "69") (name "/l_00") (class "Default")
      (node (ref "P15") (pin "22") (pinfunction "22_22") (pintype "passive"))
    )
    (net (code "70") (name "/m") (class "Default")
      (node (ref "P20") (pin "2") (pinfunction "2_2") (pintype "passive"))
      (node (ref "VR11") (pin "3") (pinfunction "3_3") (pintype "passive"))
      (node (ref "X6") (pin "15") (pinfunction "R2_3_15") (pintype "passive"))
    )
    (net (code "71") (name "/m_00") (class "Default")
      (node (ref "P15") (pin "20") (pinfunction "20_20") (pintype "passive"))
    )
    (net (code "72") (name "/m_0") (class "Default")
      (node (ref "P15") (pin "19") (pinfunction "19_19") (pintype "passive"))
      (node (ref "P20") (pin "1") (pinfunction "1_1") (pintype "passive"))
      (node (ref "VR11") (pin "1") (pinfunction "1_1") (pintype "passive"))
      (node (ref "VR11") (pin "2") (pinfunction "2_2") (pintype "passive"))
    )
    (net (code "73") (name "/n") (class "Default")
      (node (ref "P22") (pin "2") (pinfunction "2_2") (pintype "passive"))
      (node (ref "VR13") (pin "3") (pinfunction "3_3") (pintype "passive"))
      (node (ref "X6") (pin "10") (pinfunction "R1_3_10") (pintype "passive"))
    )
    (net (code "74") (name "/n_0") (class "Default")
      (node (ref "P15") (pin "17") (pinfunction "17_17") (pintype "passive"))
      (node (ref "P22") (pin "1") (pinfunction "1_1") (pintype "passive"))
      (node (ref "VR13") (pin "1") (pinfunction "1_1") (pintype "passive"))
      (node (ref "VR13") (pin "2") (pinfunction "2_2") (pintype "passive"))
    )
    (net (code "75") (name "/n_00") (class "Default")
      (node (ref "P15") (pin "18") (pinfunction "18_18") (pintype "passive"))
    )
    (net (code "76") (name "GND") (class "Default")
      (node (ref "J1") (pin "26") (pinfunction "MH1_26") (pintype "passive"))
      (node (ref "J1") (pin "27") (pinfunction "MH2_27") (pintype "passive"))
      (node (ref "J2") (pin "4") (pinfunction "GND_4") (pintype "power_in"))
      (node (ref "J3") (pin "10") (pinfunction "MH1_10") (pintype "passive"))
      (node (ref "J3") (pin "11") (pinfunction "MH2_11") (pintype "passive"))
      (node (ref "J3") (pin "2") (pinfunction "2_2") (pintype "passive"))
      (node (ref "P14") (pin "1") (pinfunction "1_1") (pintype "passive"))
      (node (ref "P14") (pin "2") (pinfunction "2_2") (pintype "passive"))
      (node (ref "P16") (pin "12") (pinfunction "12_12") (pintype "passive"))
      (node (ref "P17") (pin "14") (pinfunction "14_14") (pintype "passive"))
      (node (ref "P19") (pin "1") (pinfunction "1_1") (pintype "passive"))
      (node (ref "P19") (pin "2") (pinfunction "2_2") (pintype "passive"))
      (node (ref "P2") (pin "2") (pinfunction "2_2") (pintype "passive"))
      (node (ref "P21") (pin "1") (pinfunction "1_1") (pintype "passive"))
      (node (ref "P21") (pin "2") (pinfunction "2_2") (pintype "passive"))
      (node (ref "P23") (pin "1") (pinfunction "1_1") (pintype "passive"))
      (node (ref "P23") (pin "2") (pinfunction "2_2") (pintype "passive"))
      (node (ref "X1") (pin "12") (pinfunction "GND_12") (pintype "passive"))
      (node (ref "X10") (pin "4") (pinfunction "GND_4") (pintype "passive"))
      (node (ref "X10") (pin "5") (pinfunction "GND_5") (pintype "passive"))
      (node (ref "X10") (pin "6") (pinfunction "GND_6") (pintype "passive"))
      (node (ref "X2") (pin "12") (pinfunction "GND_12") (pintype "passive"))
      (node (ref "X3") (pin "12") (pinfunction "GND_12") (pintype "passive"))
      (node (ref "X4") (pin "12") (pinfunction "GND_12") (pintype "passive"))
      (node (ref "X5") (pin "12") (pinfunction "GND_12") (pintype "passive"))
      (node (ref "X6") (pin "12") (pinfunction "GND_12") (pintype "passive"))
      (node (ref "X7") (pin "12") (pinfunction "GND_12") (pintype "passive"))
      (node (ref "X8") (pin "11") (pinfunction "R1_4_11") (pintype "passive"))
      (node (ref "X8") (pin "12") (pinfunction "GND_12") (pintype "passive"))
      (node (ref "X8") (pin "6") (pinfunction "R1_7_6") (pintype "passive"))
    )
    (net (code "77") (name "unconnected-(J1-Pad1)") (class "Default")
      (node (ref "J1") (pin "1") (pinfunction "1_1") (pintype "passive"))
    )
    (net (code "78") (name "unconnected-(J1-Pad2)") (class "Default")
      (node (ref "J1") (pin "2") (pinfunction "2_2") (pintype "passive"))
    )
    (net (code "79") (name "unconnected-(J1-Pad3)") (class "Default")
      (node (ref "J1") (pin "3") (pinfunction "3_3") (pintype "passive"))
    )
    (net (code "80") (name "unconnected-(J1-Pad4)") (class "Default")
      (node (ref "J1") (pin "4") (pinfunction "4_4") (pintype "passive"))
    )
    (net (code "81") (name "unconnected-(J1-Pad5)") (class "Default")
      (node (ref "J1") (pin "5") (pinfunction "5_5") (pintype "passive"))
    )
    (net (code "82") (name "unconnected-(J1-Pad6)") (class "Default")
      (node (ref "J1") (pin "6") (pinfunction "6_6") (pintype "passive"))
    )
    (net (code "83") (name "unconnected-(J1-Pad7)") (class "Default")
      (node (ref "J1") (pin "7") (pinfunction "7_7") (pintype "passive"))
    )
    (net (code "84") (name "unconnected-(J1-Pad8)") (class "Default")
      (node (ref "J1") (pin "8") (pinfunction "8_8") (pintype "passive"))
    )
    (net (code "85") (name "unconnected-(J1-Pad9)") (class "Default")
      (node (ref "J1") (pin "9") (pinfunction "9_9") (pintype "passive"))
    )
    (net (code "86") (name "unconnected-(J1-Pad10)") (class "Default")
      (node (ref "J1") (pin "10") (pinfunction "10_10") (pintype "passive"))
    )
    (net (code "87") (name "unconnected-(J1-Pad11)") (class "Default")
      (node (ref "J1") (pin "11") (pinfunction "11_11") (pintype "passive"))
    )
    (net (code "88") (name "unconnected-(J1-Pad12)") (class "Default")
      (node (ref "J1") (pin "12") (pinfunction "12_12") (pintype "passive"))
    )
    (net (code "89") (name "unconnected-(J1-Pad13)") (class "Default")
      (node (ref "J1") (pin "13") (pinfunction "13_13") (pintype "passive"))
    )
    (net (code "90") (name "unconnected-(J1-Pad14)") (class "Default")
      (node (ref "J1") (pin "14") (pinfunction "14_14") (pintype "passive"))
    )
    (net (code "91") (name "unconnected-(J1-Pad15)") (class "Default")
      (node (ref "J1") (pin "15") (pinfunction "15_15") (pintype "passive"))
    )
    (net (code "92") (name "unconnected-(J1-Pad16)") (class "Default")
      (node (ref "J1") (pin "16") (pinfunction "16_16") (pintype "passive"))
    )
    (net (code "93") (name "unconnected-(J1-Pad17)") (class "Default")
      (node (ref "J1") (pin "17") (pinfunction "17_17") (pintype "passive"))
    )
    (net (code "94") (name "unconnected-(J1-Pad18)") (class "Default")
      (node (ref "J1") (pin "18") (pinfunction "18_18") (pintype "passive"))
    )
    (net (code "95") (name "unconnected-(J1-Pad19)") (class "Default")
      (node (ref "J1") (pin "19") (pinfunction "19_19") (pintype "passive"))
    )
    (net (code "96") (name "unconnected-(J1-Pad20)") (class "Default")
      (node (ref "J1") (pin "20") (pinfunction "20_20") (pintype "passive"))
    )
    (net (code "97") (name "unconnected-(J1-Pad21)") (class "Default")
      (node (ref "J1") (pin "21") (pinfunction "21_21") (pintype "passive"))
    )
    (net (code "98") (name "unconnected-(J1-Pad22)") (class "Default")
      (node (ref "J1") (pin "22") (pinfunction "22_22") (pintype "passive"))
    )
    (net (code "99") (name "unconnected-(J1-Pad23)") (class "Default")
      (node (ref "J1") (pin "23") (pinfunction "23_23") (pintype "passive"))
    )
    (net (code "100") (name "unconnected-(J1-Pad24)") (class "Default")
      (node (ref "J1") (pin "24") (pinfunction "24_24") (pintype "passive"))
    )
    (net (code "101") (name "unconnected-(J1-Pad25)") (class "Default")
      (node (ref "J1") (pin "25") (pinfunction "25_25") (pintype "passive"))
    )
    (net (code "102") (name "unconnected-(J2-SHLD-Pad5)") (class "Default")
      (node (ref "J2") (pin "5") (pinfunction "SHLD_5") (pintype "passive"))
    )
    (net (code "103") (name "unconnected-(J2-SHLD-Pad6)") (class "Default")
      (node (ref "J2") (pin "6") (pinfunction "SHLD_6") (pintype "passive"))
    )
    (net (code "104") (name "unconnected-(J2-VBUS-Pad1)") (class "Default")
      (node (ref "J2") (pin "1") (pinfunction "VBUS_1") (pintype "power_in"))
    )
    (net (code "105") (name "unconnected-(J3-Pad1)") (class "Default")
      (node (ref "J3") (pin "1") (pinfunction "1_1") (pintype "passive"))
    )
    (net (code "106") (name "unconnected-(J3-Pad3)") (class "Default")
      (node (ref "J3") (pin "3") (pinfunction "3_3") (pintype "passive"))
    )
    (net (code "107") (name "unconnected-(J3-Pad4)") (class "Default")
      (node (ref "J3") (pin "4") (pinfunction "4_4") (pintype "passive"))
    )
    (net (code "108") (name "unconnected-(J3-Pad5)") (class "Default")
      (node (ref "J3") (pin "5") (pinfunction "5_5") (pintype "passive"))
    )
    (net (code "109") (name "unconnected-(J3-Pad9)") (class "Default")
      (node (ref "J3") (pin "9") (pinfunction "9_9") (pintype "passive"))
    )
    (net (code "110") (name "unconnected-(P16-Pad7)") (class "Default")
      (node (ref "P16") (pin "7") (pinfunction "7_7") (pintype "passive"))
    )
    (net (code "111") (name "unconnected-(P16-Pad13)") (class "Default")
      (node (ref "P16") (pin "13") (pinfunction "13_13") (pintype "passive"))
    )
    (net (code "112") (name "unconnected-(P16-Pad14)") (class "Default")
      (node (ref "P16") (pin "14") (pinfunction "14_14") (pintype "passive"))
    )
    (net (code "113") (name "unconnected-(P16-Pad15)") (class "Default")
      (node (ref "P16") (pin "15") (pinfunction "15_15") (pintype "passive"))
    )
    (net (code "114") (name "unconnected-(P17-Pad2)") (class "Default")
      (node (ref "P17") (pin "2") (pinfunction "2_2") (pintype "passive"))
    )
    (net (code "115") (name "unconnected-(P17-Pad3)") (class "Default")
      (node (ref "P17") (pin "3") (pinfunction "3_3") (pintype "passive"))
    )
    (net (code "116") (name "unconnected-(P17-Pad10)") (class "Default")
      (node (ref "P17") (pin "10") (pinfunction "10_10") (pintype "passive"))
    )
    (net (code "117") (name "unconnected-(P17-Pad11)") (class "Default")
      (node (ref "P17") (pin "11") (pinfunction "11_11") (pintype "passive"))
    )
    (net (code "118") (name "unconnected-(P17-Pad12)") (class "Default")
      (node (ref "P17") (pin "12") (pinfunction "12_12") (pintype "passive"))
    )
    (net (code "119") (name "unconnected-(P17-Pad13)") (class "Default")
      (node (ref "P17") (pin "13") (pinfunction "13_13") (pintype "passive"))
    )
    (net (code "120") (name "unconnected-(P17-Pad15)") (class "Default")
      (node (ref "P17") (pin "15") (pinfunction "15_15") (pintype "passive"))
    )
    (net (code "121") (name "unconnected-(X1-R1_5-Pad4)") (class "Default")
      (node (ref "X1") (pin "4") (pinfunction "R1_5_4") (pintype "passive"))
    )
    (net (code "122") (name "unconnected-(X1-R1_6-Pad5)") (class "Default")
      (node (ref "X1") (pin "5") (pinfunction "R1_6_5") (pintype "passive"))
    )
    (net (code "123") (name "unconnected-(X1-R1_7-Pad6)") (class "Default")
      (node (ref "X1") (pin "6") (pinfunction "R1_7_6") (pintype "passive"))
    )
    (net (code "124") (name "unconnected-(X1-R2_5-Pad1)") (class "Default")
      (node (ref "X1") (pin "1") (pinfunction "R2_5_1") (pintype "passive"))
    )
    (net (code "125") (name "unconnected-(X1-R2_6-Pad2)") (class "Default")
      (node (ref "X1") (pin "2") (pinfunction "R2_6_2") (pintype "passive"))
    )
    (net (code "126") (name "unconnected-(X1-R2_7-Pad3)") (class "Default")
      (node (ref "X1") (pin "3") (pinfunction "R2_7_3") (pintype "passive"))
    )
    (net (code "127") (name "unconnected-(X2-R1_5-Pad4)") (class "Default")
      (node (ref "X2") (pin "4") (pinfunction "R1_5_4") (pintype "passive"))
    )
    (net (code "128") (name "unconnected-(X2-R1_6-Pad5)") (class "Default")
      (node (ref "X2") (pin "5") (pinfunction "R1_6_5") (pintype "passive"))
    )
    (net (code "129") (name "unconnected-(X2-R1_7-Pad6)") (class "Default")
      (node (ref "X2") (pin "6") (pinfunction "R1_7_6") (pintype "passive"))
    )
    (net (code "130") (name "unconnected-(X2-R2_5-Pad1)") (class "Default")
      (node (ref "X2") (pin "1") (pinfunction "R2_5_1") (pintype "passive"))
    )
    (net (code "131") (name "unconnected-(X2-R2_6-Pad2)") (class "Default")
      (node (ref "X2") (pin "2") (pinfunction "R2_6_2") (pintype "passive"))
    )
    (net (code "132") (name "unconnected-(X2-R2_7-Pad3)") (class "Default")
      (node (ref "X2") (pin "3") (pinfunction "R2_7_3") (pintype "passive"))
    )
    (net (code "133") (name "unconnected-(X3-R1_5-Pad4)") (class "Default")
      (node (ref "X3") (pin "4") (pinfunction "R1_5_4") (pintype "passive"))
    )
    (net (code "134") (name "unconnected-(X3-R1_6-Pad5)") (class "Default")
      (node (ref "X3") (pin "5") (pinfunction "R1_6_5") (pintype "passive"))
    )
    (net (code "135") (name "unconnected-(X3-R1_7-Pad6)") (class "Default")
      (node (ref "X3") (pin "6") (pinfunction "R1_7_6") (pintype "passive"))
    )
    (net (code "136") (name "unconnected-(X3-R2_5-Pad1)") (class "Default")
      (node (ref "X3") (pin "1") (pinfunction "R2_5_1") (pintype "passive"))
    )
    (net (code "137") (name "unconnected-(X3-R2_6-Pad2)") (class "Default")
      (node (ref "X3") (pin "2") (pinfunction "R2_6_2") (pintype "passive"))
    )
    (net (code "138") (name "unconnected-(X3-R2_7-Pad3)") (class "Default")
      (node (ref "X3") (pin "3") (pinfunction "R2_7_3") (pintype "passive"))
    )
    (net (code "139") (name "unconnected-(X4-R1_5-Pad4)") (class "Default")
      (node (ref "X4") (pin "4") (pinfunction "R1_5_4") (pintype "passive"))
    )
    (net (code "140") (name "unconnected-(X4-R1_6-Pad5)") (class "Default")
      (node (ref "X4") (pin "5") (pinfunction "R1_6_5") (pintype "passive"))
    )
    (net (code "141") (name "unconnected-(X4-R1_7-Pad6)") (class "Default")
      (node (ref "X4") (pin "6") (pinfunction "R1_7_6") (pintype "passive"))
    )
    (net (code "142") (name "unconnected-(X4-R2_5-Pad1)") (class "Default")
      (node (ref "X4") (pin "1") (pinfunction "R2_5_1") (pintype "passive"))
    )
    (net (code "143") (name "unconnected-(X4-R2_6-Pad2)") (class "Default")
      (node (ref "X4") (pin "2") (pinfunction "R2_6_2") (pintype "passive"))
    )
    (net (code "144") (name "unconnected-(X4-R2_7-Pad3)") (class "Default")
      (node (ref "X4") (pin "3") (pinfunction "R2_7_3") (pintype "passive"))
    )
    (net (code "145") (name "unconnected-(X5-R1_5-Pad4)") (class "Default")
      (node (ref "X5") (pin "4") (pinfunction "R1_5_4") (pintype "passive"))
    )
    (net (code "146") (name "unconnected-(X5-R1_6-Pad5)") (class "Default")
      (node (ref "X5") (pin "5") (pinfunction "R1_6_5") (pintype "passive"))
    )
    (net (code "147") (name "unconnected-(X5-R1_7-Pad6)") (class "Default")
      (node (ref "X5") (pin "6") (pinfunction "R1_7_6") (pintype "passive"))
    )
    (net (code "148") (name "unconnected-(X5-R2_5-Pad1)") (class "Default")
      (node (ref "X5") (pin "1") (pinfunction "R2_5_1") (pintype "passive"))
    )
    (net (code "149") (name "unconnected-(X5-R2_6-Pad2)") (class "Default")
      (node (ref "X5") (pin "2") (pinfunction "R2_6_2") (pintype "passive"))
    )
    (net (code "150") (name "unconnected-(X5-R2_7-Pad3)") (class "Default")
      (node (ref "X5") (pin "3") (pinfunction "R2_7_3") (pintype "passive"))
    )
    (net (code "151") (name "unconnected-(X6-R1_5-Pad4)") (class "Default")
      (node (ref "X6") (pin "4") (pinfunction "R1_5_4") (pintype "passive"))
    )
    (net (code "152") (name "unconnected-(X6-R1_6-Pad5)") (class "Default")
      (node (ref "X6") (pin "5") (pinfunction "R1_6_5") (pintype "passive"))
    )
    (net (code "153") (name "unconnected-(X6-R1_7-Pad6)") (class "Default")
      (node (ref "X6") (pin "6") (pinfunction "R1_7_6") (pintype "passive"))
    )
    (net (code "154") (name "unconnected-(X6-R2_5-Pad1)") (class "Default")
      (node (ref "X6") (pin "1") (pinfunction "R2_5_1") (pintype "passive"))
    )
    (net (code "155") (name "unconnected-(X6-R2_6-Pad2)") (class "Default")
      (node (ref "X6") (pin "2") (pinfunction "R2_6_2") (pintype "passive"))
    )
    (net (code "156") (name "unconnected-(X6-R2_7-Pad3)") (class "Default")
      (node (ref "X6") (pin "3") (pinfunction "R2_7_3") (pintype "passive"))
    )
    (net (code "157") (name "unconnected-(X7-R1_5-Pad4)") (class "Default")
      (node (ref "X7") (pin "4") (pinfunction "R1_5_4") (pintype "passive"))
    )
    (net (code "158") (name "unconnected-(X7-R1_6-Pad5)") (class "Default")
      (node (ref "X7") (pin "5") (pinfunction "R1_6_5") (pintype "passive"))
    )
    (net (code "159") (name "unconnected-(X7-R1_7-Pad6)") (class "Default")
      (node (ref "X7") (pin "6") (pinfunction "R1_7_6") (pintype "passive"))
    )
    (net (code "160") (name "unconnected-(X7-R2_5-Pad1)") (class "Default")
      (node (ref "X7") (pin "1") (pinfunction "R2_5_1") (pintype "passive"))
    )
    (net (code "161") (name "unconnected-(X7-R2_6-Pad2)") (class "Default")
      (node (ref "X7") (pin "2") (pinfunction "R2_6_2") (pintype "passive"))
    )
    (net (code "162") (name "unconnected-(X7-R2_7-Pad3)") (class "Default")
      (node (ref "X7") (pin "3") (pinfunction "R2_7_3") (pintype "passive"))
    )
    (net (code "163") (name "unconnected-(X8-R2_5-Pad1)") (class "Default")
      (node (ref "X8") (pin "1") (pinfunction "R2_5_1") (pintype "passive"))
    )
    (net (code "164") (name "unconnected-(X8-R2_6-Pad2)") (class "Default")
      (node (ref "X8") (pin "2") (pinfunction "R2_6_2") (pintype "passive"))
    )
    (net (code "165") (name "unconnected-(X8-R2_7-Pad3)") (class "Default")
      (node (ref "X8") (pin "3") (pinfunction "R2_7_3") (pintype "passive"))
    )
    (net (code "166") (name "unconnected-(X9-+V-Pad3)") (class "Default")
      (node (ref "X9") (pin "3") (pinfunction "+V_3") (pintype "passive"))
    )
    (net (code "167") (name "unconnected-(X9--V-Pad4)") (class "Default")
      (node (ref "X9") (pin "4") (pinfunction "-V_4") (pintype "passive"))
    )
  )
)
